# RFM69HCW_Breakout.net
KiCad netlist of a schematic drawn in EAGLE
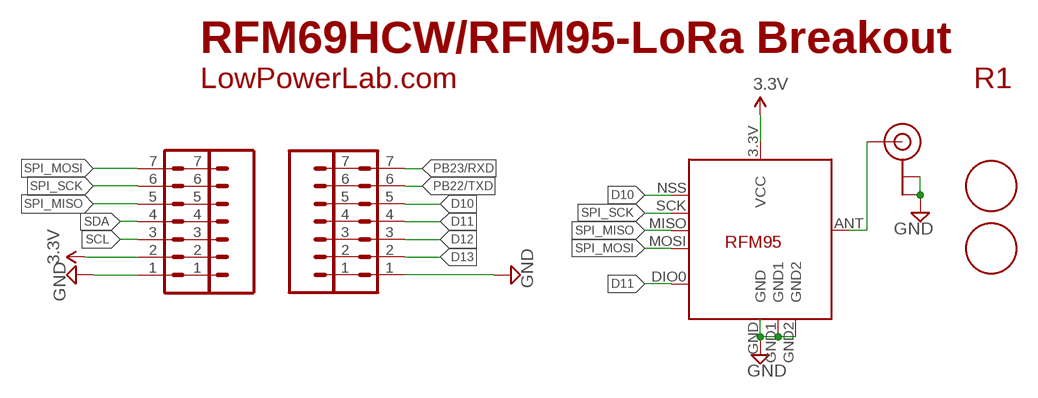
[diagram p0: schematic, sheet 1]

(export (version "E")
  (design (tool "Eeschema 10.0.6"))
  (components
    (comp (ref "FIDUCIAL_UPPERLEFT")
      (value "FIDUCIAL1.5MM")
      (footprint "eagle-import:FIDUCIAL_1.5MM")
      (libsource (lib "eagle-import") (part "FIDUCIAL1.5MM"))
    )
    (comp (ref "U$4")
      (value "HDR_7PINNS_THINRINGS")
      (footprint "eagle-import:1X07_NS_THINRINGS")
      (libsource (lib "eagle-import") (part "HDR_7PINNS_THINRINGS"))
    )
    (comp (ref "U$9")
      (value "FIDUCIAL1.5MM")
      (footprint "eagle-import:FIDUCIAL_1.5MM")
      (libsource (lib "eagle-import") (part "FIDUCIAL1.5MM"))
    )
    (comp (ref "U$10")
      (value "HDR_7PINNS_THINRINGS")
      (footprint "eagle-import:1X07_NS_THINRINGS")
      (libsource (lib "eagle-import") (part "HDR_7PINNS_THINRINGS"))
    )
    (comp (ref "U$16")
      (value "RFM95COMPACT")
      (footprint "eagle-import:RFM95")
      (libsource (lib "eagle-import") (part "RFM95COMPACT"))
    )
    (comp (ref "U$17")
      (value "HDR_7PINHH")
      (footprint "eagle-import:1X07_NS_THINRINGS_HH")
      (libsource (lib "eagle-import") (part "HDR_7PINHH"))
    )
    (comp (ref "U$18")
      (value "HDR_7PINHH")
      (footprint "eagle-import:1X07_NS_THINRINGS_HH")
      (libsource (lib "eagle-import") (part "HDR_7PINHH"))
    )
    (comp (ref "X2")
      (value "U.FLW")
      (footprint "eagle-import:U.FL_WIDER")
      (libsource (lib "eagle-import") (part "U.FLW"))
    )
  )
  (nets
    (net (code "1") (name "3.3V") (class "Default")
      (node (ref "U$16") (pin "3.3V") (pinfunction "VCC_3.3V") (pintype "power_in"))
      (node (ref "U$18") (pin "2") (pinfunction "2_2") (pintype "passive"))
    )
    (net (code "2") (name "D10") (class "Default")
      (node (ref "U$16") (pin "NSS") (pinfunction "SEL_NSS") (pintype "input"))
      (node (ref "U$17") (pin "5") (pinfunction "5_5") (pintype "passive"))
    )
    (net (code "3") (name "D11") (class "Default")
      (node (ref "U$16") (pin "DIO0") (pinfunction "DIO0_DIO0") (pintype "open_collector"))
      (node (ref "U$17") (pin "4") (pinfunction "4_4") (pintype "passive"))
    )
    (net (code "4") (name "D12") (class "Default")
      (node (ref "U$17") (pin "3") (pinfunction "3_3") (pintype "passive"))
    )
    (net (code "5") (name "D13") (class "Default")
      (node (ref "U$17") (pin "2") (pinfunction "2_2") (pintype "passive"))
    )
    (net (code "6") (name "GND") (class "Default")
      (node (ref "U$16") (pin "GND") (pinfunction "GND_GND") (pintype "power_in"))
      (node (ref "U$16") (pin "GND1") (pinfunction "GND1_GND1") (pintype "power_in"))
      (node (ref "U$16") (pin "GND2") (pinfunction "GND2_GND2") (pintype "power_in"))
      (node (ref "U$17") (pin "1") (pinfunction "1_1") (pintype "passive"))
      (node (ref "U$18") (pin "1") (pinfunction "1_1") (pintype "passive"))
      (node (ref "X2") (pin "GND1") (pinfunction "GND_GND1") (pintype "bidirectional"))
      (node (ref "X2") (pin "GND2") (pinfunction "GND_GND2") (pintype "bidirectional"))
    )
    (net (code "7") (name "Net-(U$16-PadANT)") (class "Default")
      (node (ref "U$16") (pin "ANT") (pinfunction "ANT_ANT") (pintype "passive"))
      (node (ref "X2") (pin "SIGNAL") (pinfunction "SIGNAL_SIGNAL") (pintype "bidirectional"))
    )
    (net (code "8") (name "PB22{slash}TXD") (class "Default")
      (node (ref "U$17") (pin "6") (pinfunction "6_6") (pintype "passive"))
    )
    (net (code "9") (name "PB23{slash}RXD") (class "Default")
      (node (ref "U$17") (pin "7") (pinfunction "7_7") (pintype "passive"))
    )
    (net (code "10") (name "SCL") (class "Default")
      (node (ref "U$18") (pin "3") (pinfunction "3_3") (pintype "passive"))
    )
    (net (code "11") (name "SDA") (class "Default")
      (node (ref "U$18") (pin "4") (pinfunction "4_4") (pintype "passive"))
    )
    (net (code "12") (name "SPI_MISO") (class "Default")
      (node (ref "U$16") (pin "MISO") (pinfunction "MISO_MISO") (pintype "input"))
      (node (ref "U$18") (pin "5") (pinfunction "5_5") (pintype "passive"))
    )
    (net (code "13") (name "SPI_MOSI") (class "Default")
      (node (ref "U$16") (pin "MOSI") (pinfunction "MOSI_MOSI") (pintype "output"))
      (node (ref "U$18") (pin "7") (pinfunction "7_7") (pintype "passive"))
    )
    (net (code "14") (name "SPI_SCK") (class "Default")
      (node (ref "U$16") (pin "SCK") (pinfunction "SCK_SCK") (pintype "input"))
      (node (ref "U$18") (pin "6") (pinfunction "6_6") (pintype "passive"))
    )
    (net (code "15") (name "unconnected-(FIDUCIAL_UPPERLEFT-FIDUCIAL-PadP$1)") (class "Default")
      (node (ref "FIDUCIAL_UPPERLEFT") (pin "P$1") (pinfunction "FIDUCIAL_P$1") (pintype "bidirectional"))
    )
    (net (code "16") (name "unconnected-(U$4-Pad1)") (class "Default")
      (node (ref "U$4") (pin "1") (pinfunction "1_1") (pintype "passive"))
    )
    (net (code "17") (name "unconnected-(U$4-Pad2)") (class "Default")
      (node (ref "U$4") (pin "2") (pinfunction "2_2") (pintype "passive"))
    )
    (net (code "18") (name "unconnected-(U$4-Pad3)") (class "Default")
      (node (ref "U$4") (pin "3") (pinfunction "3_3") (pintype "passive"))
    )
    (net (code "19") (name "unconnected-(U$4-Pad4)") (class "Default")
      (node (ref "U$4") (pin "4") (pinfunction "4_4") (pintype "passive"))
    )
    (net (code "20") (name "unconnected-(U$4-Pad5)") (class "Default")
      (node (ref "U$4") (pin "5") (pinfunction "5_5") (pintype "passive"))
    )
    (net (code "21") (name "unconnected-(U$4-Pad6)") (class "Default")
      (node (ref "U$4") (pin "6") (pinfunction "6_6") (pintype "passive"))
    )
    (net (code "22") (name "unconnected-(U$4-Pad7)") (class "Default")
      (node (ref "U$4") (pin "7") (pinfunction "7_7") (pintype "passive"))
    )
    (net (code "23") (name "unconnected-(U$9-FIDUCIAL-PadP$1)") (class "Default")
      (node (ref "U$9") (pin "P$1") (pinfunction "FIDUCIAL_P$1") (pintype "bidirectional"))
    )
    (net (code "24") (name "unconnected-(U$10-Pad1)") (class "Default")
      (node (ref "U$10") (pin "1") (pinfunction "1_1") (pintype "passive"))
    )
    (net (code "25") (name "unconnected-(U$10-Pad2)") (class "Default")
      (node (ref "U$10") (pin "2") (pinfunction "2_2") (pintype "passive"))
    )
    (net (code "26") (name "unconnected-(U$10-Pad3)") (class "Default")
      (node (ref "U$10") (pin "3") (pinfunction "3_3") (pintype "passive"))
    )
    (net (code "27") (name "unconnected-(U$10-Pad4)") (class "Default")
      (node (ref "U$10") (pin "4") (pinfunction "4_4") (pintype "passive"))
    )
    (net (code "28") (name "unconnected-(U$10-Pad5)") (class "Default")
      (node (ref "U$10") (pin "5") (pinfunction "5_5") (pintype "passive"))
    )
    (net (code "29") (name "unconnected-(U$10-Pad6)") (class "Default")
      (node (ref "U$10") (pin "6") (pinfunction "6_6") (pintype "passive"))
    )
    (net (code "30") (name "unconnected-(U$10-Pad7)") (class "Default")
      (node (ref "U$10") (pin "7") (pinfunction "7_7") (pintype "passive"))
    )
  )
)
